# 1_47.net
KiCad netlist of a schematic drawn in Altium Designer
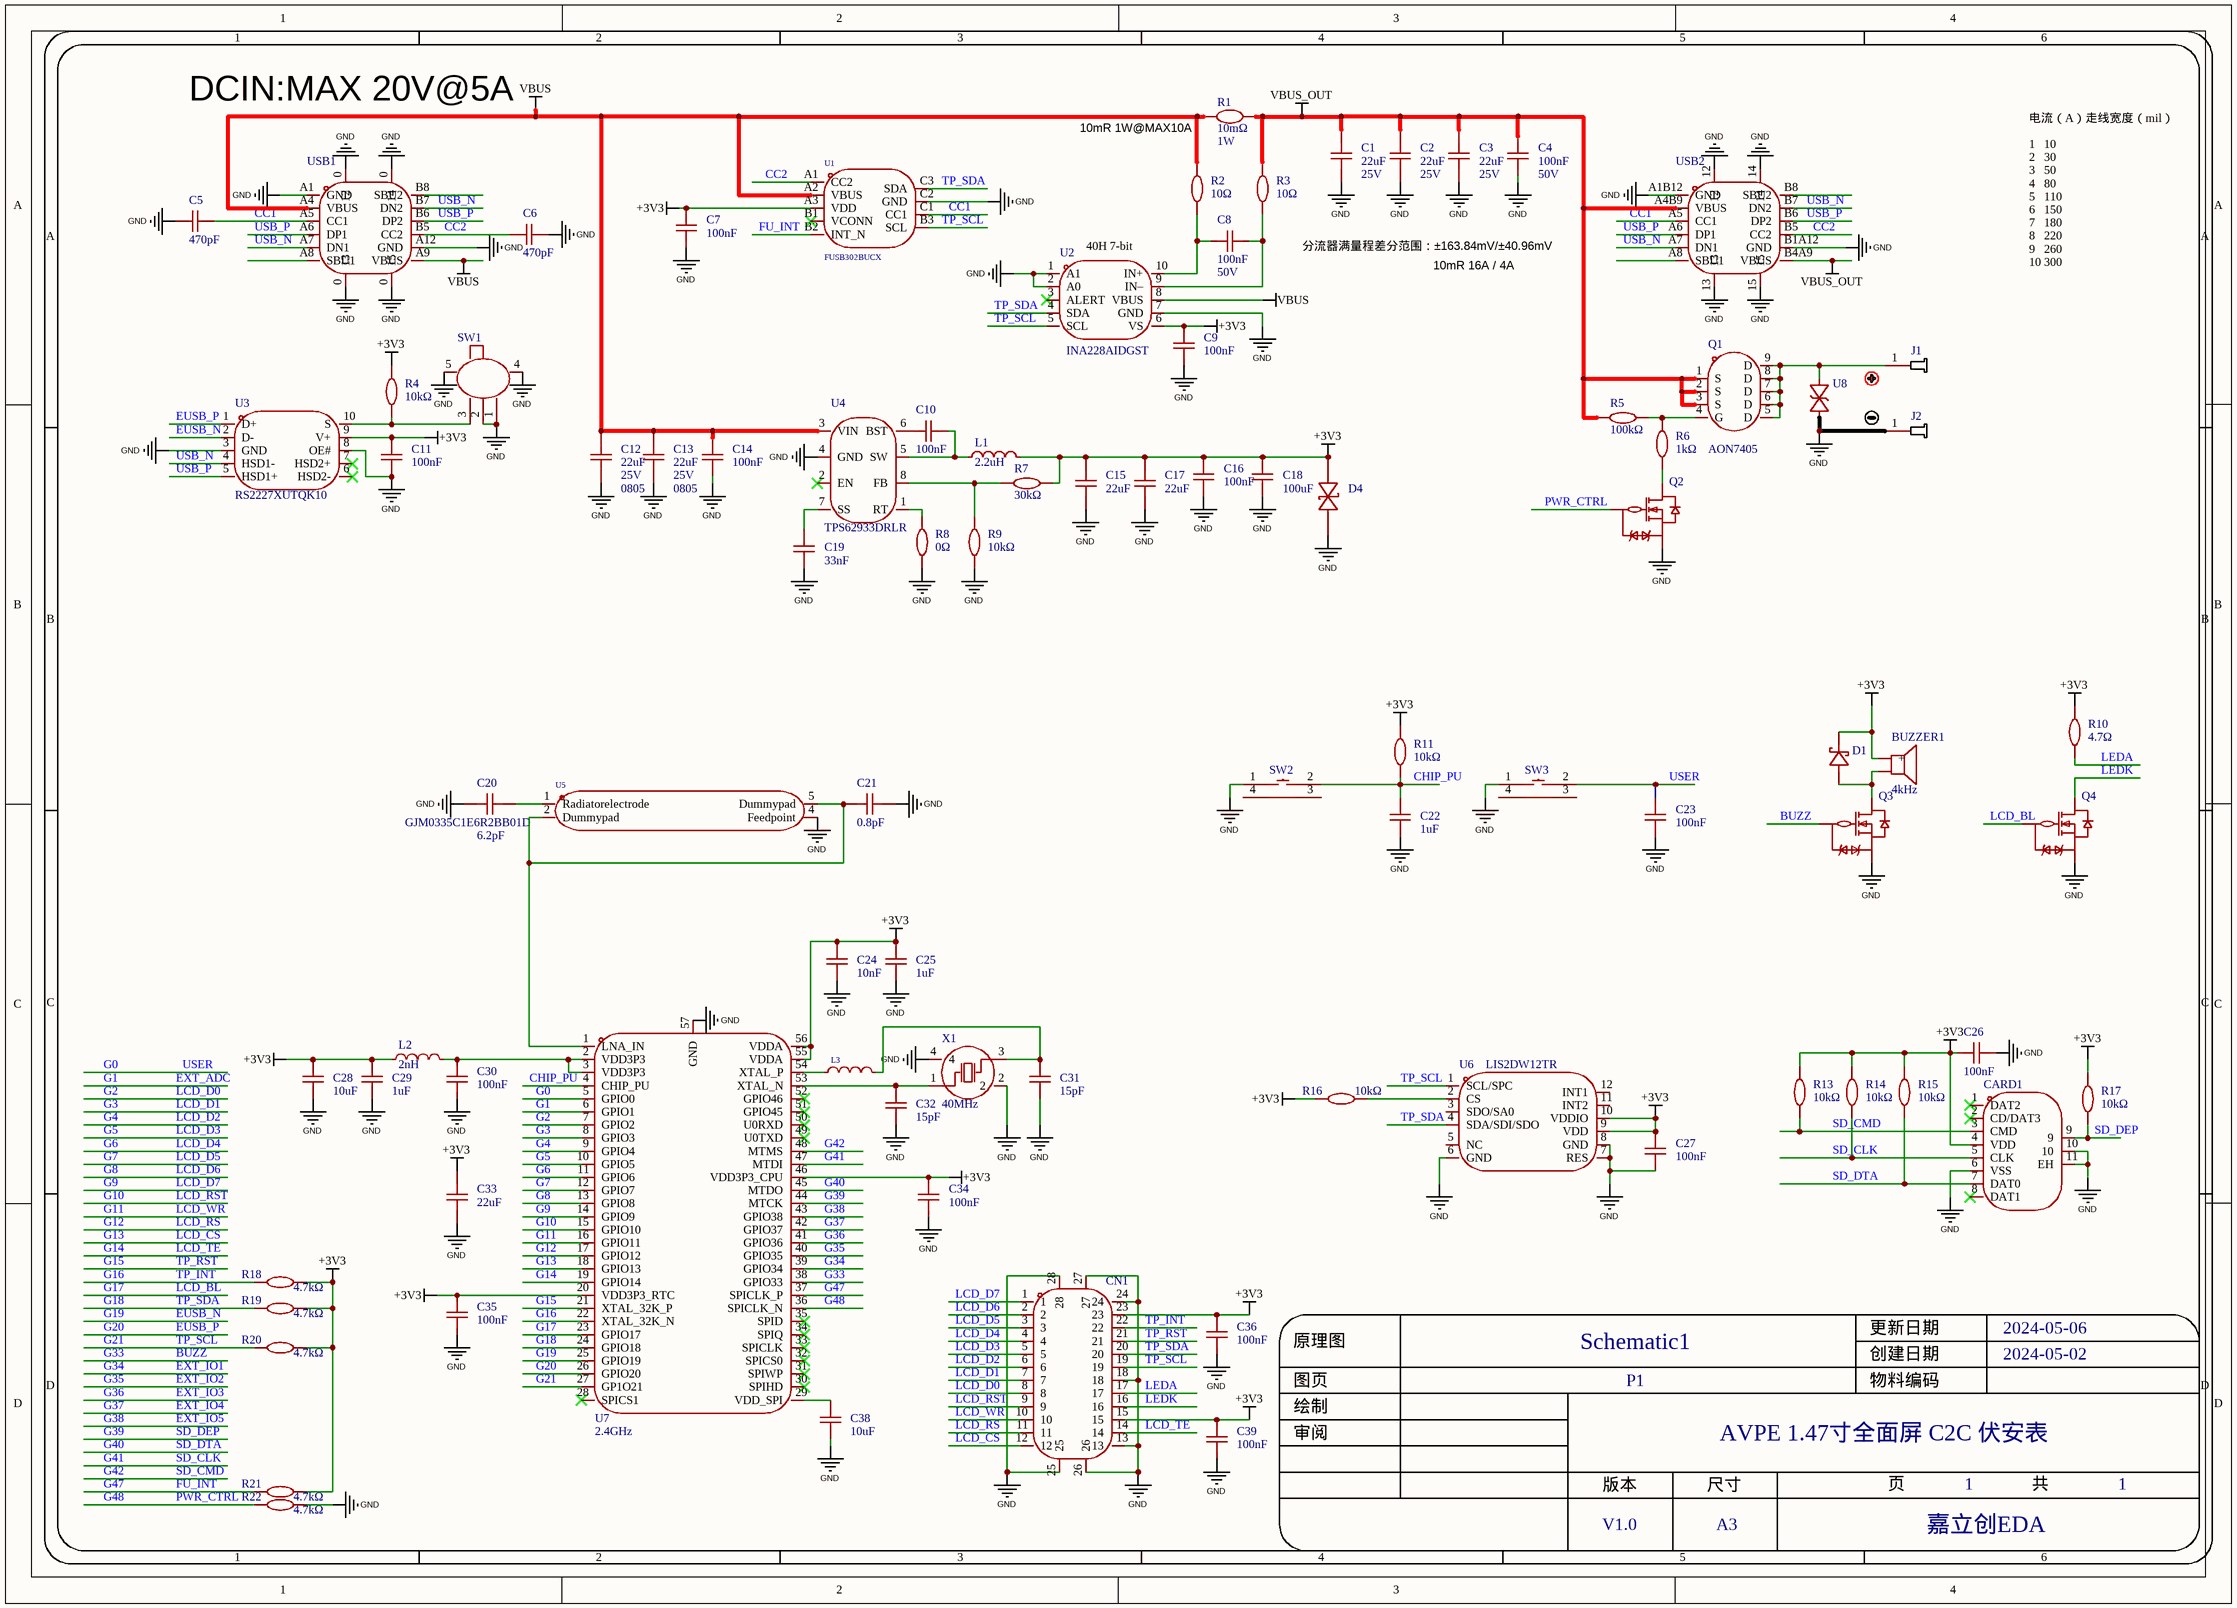
[diagram p0: 1.47.schdoc]

(export (version "E")
  (design (tool "Eeschema 10.0.6"))
  (components
    (comp (ref "BUZZER1")
      (value "4kHz")
      (footprint "BUZ-SMD_L4.0-W4.0-P3.50-L")
      (description "驱动方式:无源(外部驱动);构造类型:电磁式;频率:4kHz;声压(SPL):65dB@3V,10cm;")
      (fields (field (name "MANUFACTURER") "FUET(福声科技)") (field (name "MANUFACTURER PART") "FUET-4020"))
      (libsource (lib "altium-import") (part "root_0_FUET-4020_"))
    )
    (comp (ref "C1")
      (value "22uF")
      (footprint "C1206")
      (description "容值:22uF;精度:±10%;额定电压:25V;材质(温度系数):X5R;")
      (fields
        (field (name "MANUFACTURER") "Chinocera(华瓷)")
        (field (name "MANUFACTURER PART") "HGC1206R5226K250NSPJ")
        (field (name "VOLTAGE RATED") "25V")
      )
      (libsource (lib "altium-import") (part "root_1_HGC1206R5226K250NSPJ_"))
    )
    (comp (ref "C2")
      (value "22uF")
      (footprint "C1206")
      (description "容值:22uF;精度:±10%;额定电压:25V;材质(温度系数):X5R;")
      (fields
        (field (name "MANUFACTURER") "Chinocera(华瓷)")
        (field (name "MANUFACTURER PART") "HGC1206R5226K250NSPJ")
        (field (name "VOLTAGE RATED") "25V")
      )
      (libsource (lib "altium-import") (part "root_1_HGC1206R5226K250NSPJ_"))
    )
    (comp (ref "C3")
      (value "22uF")
      (footprint "C1206")
      (description "容值:22uF;精度:±10%;额定电压:25V;材质(温度系数):X5R;")
      (fields
        (field (name "MANUFACTURER") "Chinocera(华瓷)")
        (field (name "MANUFACTURER PART") "HGC1206R5226K250NSPJ")
        (field (name "VOLTAGE RATED") "25V")
      )
      (libsource (lib "altium-import") (part "root_1_HGC1206R5226K250NSPJ_"))
    )
    (comp (ref "C4")
      (value "100nF")
      (footprint "C0402")
      (description "容值:100nF;精度:±10%;额定电压:50V;材质(温度系数):X7R;")
      (fields
        (field (name "MANUFACTURER") "SAMSUNG(三星)")
        (field (name "MANUFACTURER PART") "CL05B104KB54PNC")
        (field (name "VOLTAGE RATED") "50V")
      )
      (libsource (lib "altium-import") (part "root_1_CL05B104KB54PNC_"))
    )
    (comp (ref "C5")
      (value "470pF")
      (footprint "C0402")
      (description "容值:470pF;精度:±10%;额定电压:50V;材质(温度系数):X7R;")
      (fields (field (name "MANUFACTURER") "FH(风华)") (field (name "MANUFACTURER PART") "0402B471K500NT"))
      (libsource (lib "altium-import") (part "root_2_0402B471K500NT_"))
    )
    (comp (ref "C6")
      (value "470pF")
      (footprint "C0402")
      (description "容值:470pF;精度:±10%;额定电压:50V;材质(温度系数):X7R;")
      (fields (field (name "MANUFACTURER") "FH(风华)") (field (name "MANUFACTURER PART") "0402B471K500NT"))
      (libsource (lib "altium-import") (part "root_2_0402B471K500NT_"))
    )
    (comp (ref "C7")
      (value "100nF")
      (footprint "C0402")
      (description "容值:100nF;精度:±10%;额定电压:50V;材质(温度系数):X7R;")
      (fields
        (field (name "MANUFACTURER") "SAMSUNG(三星)")
        (field (name "MANUFACTURER PART") "CL05B104KB54PNC")
      )
      (libsource (lib "altium-import") (part "root_3_CL05B104KB54PNC_"))
    )
    (comp (ref "C8")
      (value "100nF")
      (footprint "C0402")
      (description "容值:100nF;精度:±10%;额定电压:50V;材质(温度系数):X7R;")
      (fields
        (field (name "MANUFACTURER") "SAMSUNG(三星)")
        (field (name "MANUFACTURER PART") "CL05B104KB54PNC")
        (field (name "VOLTAGE RATED") "50V")
      )
      (libsource (lib "altium-import") (part "root_2_CL05B104KB54PNC_"))
    )
    (comp (ref "C9")
      (value "100nF")
      (footprint "C0402")
      (description "容值:100nF;精度:±10%;额定电压:50V;材质(温度系数):X7R;")
      (fields
        (field (name "MANUFACTURER") "SAMSUNG(三星)")
        (field (name "MANUFACTURER PART") "CL05B104KB54PNC")
      )
      (libsource (lib "altium-import") (part "root_3_CL05B104KB54PNC_"))
    )
    (comp (ref "C10")
      (value "100nF")
      (footprint "C0402")
      (description "容值:100nF;精度:±10%;额定电压:50V;材质(温度系数):X7R;")
      (fields
        (field (name "MANUFACTURER") "SAMSUNG(三星)")
        (field (name "MANUFACTURER PART") "CL05B104KB54PNC")
      )
      (libsource (lib "altium-import") (part "root_2_CL05B104KB54PNC_"))
    )
    (comp (ref "C11")
      (value "100nF")
      (footprint "C0402")
      (description "容值:100nF;精度:±10%;额定电压:50V;材质(温度系数):X7R;")
      (fields
        (field (name "MANUFACTURER") "SAMSUNG(三星)")
        (field (name "MANUFACTURER PART") "CL05B104KB54PNC")
      )
      (libsource (lib "altium-import") (part "root_3_CL05B104KB54PNC_"))
    )
    (comp (ref "C12")
      (value "22uF")
      (footprint "C0805")
      (description "容值:22uF;精度:±20%;额定电压:25V;材质(温度系数):X5R;")
      (fields
        (field (name "MANUFACTURER") "SAMSUNG(三星)")
        (field (name "MANUFACTURER PART") "CL21A226MAYNNNE")
        (field (name "SUPPLIER FOOTPRINT") "0805")
        (field (name "VOLTAGE RATED") "25V")
      )
      (libsource (lib "altium-import") (part "root_1_CL21A226MAYNNNE_"))
    )
    (comp (ref "C13")
      (value "22uF")
      (footprint "C0805")
      (description "容值:22uF;精度:±20%;额定电压:25V;材质(温度系数):X5R;")
      (fields
        (field (name "MANUFACTURER") "SAMSUNG(三星)")
        (field (name "MANUFACTURER PART") "CL21A226MAYNNNE")
        (field (name "SUPPLIER FOOTPRINT") "0805")
        (field (name "VOLTAGE RATED") "25V")
      )
      (libsource (lib "altium-import") (part "root_1_CL21A226MAYNNNE_"))
    )
    (comp (ref "C14")
      (value "100nF")
      (footprint "C0402")
      (description "容值:100nF;精度:±10%;额定电压:50V;材质(温度系数):X7R;")
      (fields
        (field (name "MANUFACTURER") "SAMSUNG(三星)")
        (field (name "MANUFACTURER PART") "CL05B104KB54PNC")
      )
      (libsource (lib "altium-import") (part "root_3_CL05B104KB54PNC_"))
    )
    (comp (ref "C15")
      (value "22uF")
      (footprint "C0603")
      (description "容值:22uF;精度:±20%;额定电压:10V;材质(温度系数):X5R;")
      (fields
        (field (name "MANUFACTURER") "SAMSUNG(三星)")
        (field (name "MANUFACTURER PART") "CL10A226MP8NUNE")
      )
      (libsource (lib "altium-import") (part "root_1_CL10A226MP8NUNE_"))
    )
    (comp (ref "C16")
      (value "100nF")
      (footprint "C0402")
      (description "容值:100nF;精度:±10%;额定电压:50V;材质(温度系数):X7R;")
      (fields
        (field (name "MANUFACTURER") "SAMSUNG(三星)")
        (field (name "MANUFACTURER PART") "CL05B104KB54PNC")
      )
      (libsource (lib "altium-import") (part "root_3_CL05B104KB54PNC_"))
    )
    (comp (ref "C17")
      (value "22uF")
      (footprint "C0603")
      (description "容值:22uF;精度:±20%;额定电压:10V;材质(温度系数):X5R;")
      (fields
        (field (name "MANUFACTURER") "SAMSUNG(三星)")
        (field (name "MANUFACTURER PART") "CL10A226MP8NUNE")
      )
      (libsource (lib "altium-import") (part "root_1_CL10A226MP8NUNE_"))
    )
    (comp (ref "C18")
      (value "100uF")
      (footprint "C1206")
      (description "容值:100uF;精度:±20%;额定电压:6.3V;材质(温度系数):X5R;")
      (fields
        (field (name "MANUFACTURER PART") "CL31A107MQHNNNE")
        (field (name "MANUFACTURER") "SAMSUNG(三星)")
      )
      (libsource (lib "altium-import") (part "root_1_CL31A107MQHNNNE_"))
    )
    (comp (ref "C19")
      (value "33nF")
      (footprint "C0402")
      (description "容值:33nF;精度:±10%;额定电压:50V;材质(温度系数):X7R;")
      (fields
        (field (name "MANUFACTURER") "YAGEO(国巨)")
        (field (name "MANUFACTURER PART") "CC0402KRX7R9BB333")
      )
      (libsource (lib "altium-import") (part "root_1_CC0402KRX7R9BB333_"))
    )
    (comp (ref "C20")
      (value "6.2pF")
      (footprint "C0201")
      (description "容值:0.8pF;额定电压:25V;材质(温度系数):C0G;")
      (fields
        (field (name "MANUFACTURER") "muRata(村田)")
        (field (name "MANUFACTURER PART") "GJM0335C1E6R2BB01D")
      )
      (libsource (lib "altium-import") (part "root_2_mirrored_GJM0335C1ER80WB01D_"))
    )
    (comp (ref "C21")
      (value "0.8pF")
      (footprint "C0402")
      (description "容值:0.8pF;额定电压:25V;材质(温度系数):C0G;")
      (fields
        (field (name "MANUFACTURER") "muRata(村田)")
        (field (name "MANUFACTURER PART") "GJM0335C1ER80WB01D")
      )
      (libsource (lib "altium-import") (part "root_2_mirrored_GJM0335C1ER80WB01D_"))
    )
    (comp (ref "C22")
      (value "1uF")
      (footprint "C0402")
      (description "容值:1uF;精度:±10%;额定电压:10V;材质(温度系数):X5R;")
      (fields
        (field (name "MANUFACTURER PART") "CL05A105KP5NNNC")
        (field (name "MANUFACTURER") "SAMSUNG(三星)")
      )
      (libsource (lib "altium-import") (part "root_1_CL05A105KP5NNNC_"))
    )
    (comp (ref "C23")
      (value "100nF")
      (footprint "C0402")
      (description "容值:100nF;精度:±10%;额定电压:50V;材质(温度系数):X7R;")
      (fields
        (field (name "MANUFACTURER") "SAMSUNG(三星)")
        (field (name "MANUFACTURER PART") "CL05B104KB54PNC")
      )
      (libsource (lib "altium-import") (part "root_3_CL05B104KB54PNC_"))
    )
    (comp (ref "C24")
      (value "10nF")
      (footprint "C0402")
      (description "容值:10nF;精度:±10%;额定电压:50V;材质(温度系数):X7R;")
      (fields
        (field (name "MANUFACTURER") "SAMSUNG(三星)")
        (field (name "MANUFACTURER PART") "CL05B103KB5NNNC")
      )
      (libsource (lib "altium-import") (part "root_1_CL05B103KB5NNNC_"))
    )
    (comp (ref "C25")
      (value "1uF")
      (footprint "C0402")
      (description "容值:1uF;精度:±10%;额定电压:10V;材质(温度系数):X5R;")
      (fields
        (field (name "MANUFACTURER PART") "CL05A105KP5NNNC")
        (field (name "MANUFACTURER") "SAMSUNG(三星)")
      )
      (libsource (lib "altium-import") (part "root_1_CL05A105KP5NNNC_"))
    )
    (comp (ref "C26")
      (value "100nF")
      (footprint "C0402")
      (description "容值:100nF;精度:±10%;额定电压:50V;材质(温度系数):X7R;")
      (fields
        (field (name "MANUFACTURER") "SAMSUNG(三星)")
        (field (name "MANUFACTURER PART") "CL05B104KB54PNC")
      )
      (libsource (lib "altium-import") (part "root_0_CL05B104KB54PNC_"))
    )
    (comp (ref "C27")
      (value "100nF")
      (footprint "C0402")
      (description "容值:100nF;精度:±10%;额定电压:50V;材质(温度系数):X7R;")
      (fields
        (field (name "MANUFACTURER") "SAMSUNG(三星)")
        (field (name "MANUFACTURER PART") "CL05B104KB54PNC")
      )
      (libsource (lib "altium-import") (part "root_1_CL05B104KB54PNC_"))
    )
    (comp (ref "C28")
      (value "10uF")
      (footprint "C0402")
      (description "容值:10uF;精度:±20%;额定电压:6.3V;材质(温度系数):X5R;")
      (fields
        (field (name "MANUFACTURER PART") "CL05A106MQ5NUNC")
        (field (name "MANUFACTURER") "SAMSUNG(三星)")
      )
      (libsource (lib "altium-import") (part "root_1_CL05A106MQ5NUNC_"))
    )
    (comp (ref "C29")
      (value "1uF")
      (footprint "C0402")
      (description "容值:1uF;精度:±10%;额定电压:10V;材质(温度系数):X5R;")
      (fields
        (field (name "MANUFACTURER PART") "CL05A105KP5NNNC")
        (field (name "MANUFACTURER") "SAMSUNG(三星)")
      )
      (libsource (lib "altium-import") (part "root_1_CL05A105KP5NNNC_"))
    )
    (comp (ref "C30")
      (value "100nF")
      (footprint "C0402")
      (description "容值:100nF;精度:±10%;额定电压:50V;材质(温度系数):X7R;")
      (fields
        (field (name "MANUFACTURER") "SAMSUNG(三星)")
        (field (name "MANUFACTURER PART") "CL05B104KB54PNC")
      )
      (libsource (lib "altium-import") (part "root_3_CL05B104KB54PNC_"))
    )
    (comp (ref "C31")
      (value "15pF")
      (footprint "C0402")
      (description "容值:15pF;精度:±5%;额定电压:50V;材质(温度系数):C0G;")
      (fields (field (name "MANUFACTURER") "FH(风华)") (field (name "MANUFACTURER PART") "0402CG150J500NT"))
      (libsource (lib "altium-import") (part "root_1_0402CG150J500NT_"))
    )
    (comp (ref "C32")
      (value "15pF")
      (footprint "C0402")
      (description "容值:15pF;精度:±5%;额定电压:50V;材质(温度系数):C0G;")
      (fields (field (name "MANUFACTURER") "FH(风华)") (field (name "MANUFACTURER PART") "0402CG150J500NT"))
      (libsource (lib "altium-import") (part "root_1_0402CG150J500NT_"))
    )
    (comp (ref "C33")
      (value "22uF")
      (footprint "C0603")
      (description "容值:22uF;精度:±20%;额定电压:10V;材质(温度系数):X5R;")
      (fields
        (field (name "MANUFACTURER") "SAMSUNG(三星)")
        (field (name "MANUFACTURER PART") "CL10A226MP8NUNE")
      )
      (libsource (lib "altium-import") (part "root_1_CL10A226MP8NUNE_"))
    )
    (comp (ref "C34")
      (value "100nF")
      (footprint "C0402")
      (description "容值:100nF;精度:±10%;额定电压:50V;材质(温度系数):X7R;")
      (fields
        (field (name "MANUFACTURER") "SAMSUNG(三星)")
        (field (name "MANUFACTURER PART") "CL05B104KB54PNC")
      )
      (libsource (lib "altium-import") (part "root_3_mirrored_CL05B104KB54PNC_"))
    )
    (comp (ref "C35")
      (value "100nF")
      (footprint "C0402")
      (description "容值:100nF;精度:±10%;额定电压:50V;材质(温度系数):X7R;")
      (fields
        (field (name "MANUFACTURER") "SAMSUNG(三星)")
        (field (name "MANUFACTURER PART") "CL05B104KB54PNC")
      )
      (libsource (lib "altium-import") (part "root_3_CL05B104KB54PNC_"))
    )
    (comp (ref "C36")
      (value "100nF")
      (footprint "C0402")
      (description "容值:100nF;精度:±10%;额定电压:50V;材质(温度系数):X7R;")
      (fields
        (field (name "MANUFACTURER") "SAMSUNG(三星)")
        (field (name "MANUFACTURER PART") "CL05B104KB54PNC")
      )
      (libsource (lib "altium-import") (part "root_3_mirrored_CL05B104KB54PNC_"))
    )
    (comp (ref "C38")
      (value "10uF")
      (footprint "C0402")
      (description "容值:10uF;精度:±20%;额定电压:6.3V;材质(温度系数):X5R;")
      (fields
        (field (name "MANUFACTURER PART") "CL05A106MQ5NUNC")
        (field (name "MANUFACTURER") "SAMSUNG(三星)")
      )
      (libsource (lib "altium-import") (part "root_1_CL05A106MQ5NUNC_"))
    )
    (comp (ref "C39")
      (value "100nF")
      (footprint "C0402")
      (description "容值:100nF;精度:±10%;额定电压:50V;材质(温度系数):X7R;")
      (fields
        (field (name "MANUFACTURER") "SAMSUNG(三星)")
        (field (name "MANUFACTURER PART") "CL05B104KB54PNC")
      )
      (libsource (lib "altium-import") (part "root_3_mirrored_CL05B104KB54PNC_"))
    )
    (comp (ref "CARD1")
      (value "5033981892")
      (footprint "TF-SMD_TF-110")
      (description "卡连接方式:自弹式;卡类型:MicroSD卡(TF卡);连接器类型:卡座;本体最大高度:1.28mm;触头镀层:金;工作温度范围:-25℃~+85℃;")
      (fields (field (name "MANUFACTURER") "MOLEX"))
      (libsource (lib "altium-import") (part "root_0_5033981892_"))
    )
    (comp (ref "CN1")
      (value "BM20B(0.8)-24DS-0.4V(51)")
      (footprint "CONN-SMD_BM20B-0.8-24DS-0.4V-51")
      (description "PIN总数:-;间距:0.4mm;公母:母;安装方式:立贴;行数:2;额定电流:300mA;工作温度范围:-35℃~+85℃;")
      (fields (field (name "MANUFACTURER") "HRS(广濑)"))
      (libsource (lib "1.47") (part "BM20B(0.8)-24DS-0.4V(51)"))
    )
    (comp (ref "D1")
      (value "1N4148WT")
      (footprint "SOD-523_L1.2-W0.8-LS1.6-RD")
      (description "二极管配置:独立式;正向压降(Vf):1.25V@150mA;直流反向耐压(Vr):75V;平均整流电流(Io):125mA;反向恢复时间(trr):4ns;")
      (fields (field (name "MANUFACTURER") "TWGMC(台湾迪嘉)"))
      (libsource (lib "altium-import") (part "root_3_1N4148WT_C727112_"))
    )
    (comp (ref "D4")
      (value "BDFN2C031V")
      (footprint "TSSLP-2-4_L1.0-W0.6-P0.65-BI")
      (description "反向截止电压(Vrwm):3.3V;最大钳位电压:8V;峰值脉冲电流(Ipp)@10/1000us:11A@8/20us;击穿电压:3.7V;")
      (fields (field (name "MANUFACTURER") "BORN(伯恩半导体)"))
      (libsource (lib "altium-import") (part "root_1_BDFN2C031V_"))
    )
    (comp (ref "J1")
      (value "~")
      (footprint "Banana_M2xφ4.4x7_2")
      (description "K2台阶插座,Banana_M2xφ4.4x7")
      (libsource (lib "altium-import") (part "root_0_Banana_M2xφ4.4x7_"))
    )
    (comp (ref "J2")
      (value "~")
      (footprint "Banana_M2xφ4.4x7_2")
      (description "K2台阶插座,Banana_M2xφ4.4x7")
      (libsource (lib "altium-import") (part "root_0_Banana_M2xφ4.4x7_"))
    )
    (comp (ref "L1")
      (value "2.2uH")
      (footprint "L0805")
      (description "电感值:2.2uH;精度:±20%;额定电流:1A;")
      (fields (field (name "MANUFACTURER") "TDK") (field (name "MANUFACTURER PART") "MLP2012H2R2MT0S1"))
      (libsource (lib "altium-import") (part "root_0_MLP2012H2R2MT0S1_"))
    )
    (comp (ref "L2")
      (value "2nH")
      (footprint "L0402")
      (description "电感值:2nH;精度:-;额定电流:300mA;饱和电流(Isat):-;直流电阻(DCR):200mΩ;")
      (fields
        (field (name "MANUFACTURER") "Sunlord(顺络)")
        (field (name "MANUFACTURER PART") "SDCL1005C2N0STDF")
      )
      (libsource (lib "altium-import") (part "root_0_SDCL1005C2N0STDF_"))
    )
    (comp (ref "L3")
      (value "27nH")
      (footprint "IND-SMD_L1.0-W0.5-2")
      (description "电感值:27nH;精度:±2%;额定电流:280mA;饱和电流(Isat):-;")
      (fields (field (name "MANUFACTURER") "muRata(村田)") (field (name "MANUFACTURER PART") "LQW15AN27NG00D"))
      (libsource (lib "altium-import") (part "root_0_LQW15AN27NG00D_"))
    )
    (comp (ref "Q1")
      (value "AON7405")
      (footprint "DFN-8_L3.3-W3.3-P0.65-BL-3")
      (fields (field (name "MANUFACTURER") "AOS") (field (name "MANUFACTURER PART") "AON7405"))
      (libsource (lib "altium-import") (part "root_0_AON7405_"))
    )
    (comp (ref "Q2")
      (value "WNM6002-3/TR")
      (footprint "SOT-323-3_L2.0-W1.3-P1.30-LS2.1-BR")
      (fields (field (name "MANUFACTURER") "WILLSEMI(韦尔)"))
      (libsource (lib "altium-import") (part "root_0_WNM6002-3/TR_"))
    )
    (comp (ref "Q3")
      (value "WNM6002-3/TR")
      (footprint "SOT-323-3_L2.0-W1.3-P1.30-LS2.1-BR")
      (fields (field (name "MANUFACTURER") "WILLSEMI(韦尔)"))
      (libsource (lib "altium-import") (part "root_0_WNM6002-3/TR_"))
    )
    (comp (ref "Q4")
      (value "WNM6002-3/TR")
      (footprint "SOT-323-3_L2.0-W1.3-P1.30-LS2.1-BR")
      (fields (field (name "MANUFACTURER") "WILLSEMI(韦尔)"))
      (libsource (lib "altium-import") (part "root_0_WNM6002-3/TR_"))
    )
    (comp (ref "R1")
      (value "10mΩ")
      (footprint "RES-SMD_L6.3-W3.3_HOLR2512")
      (description "电阻类型:采样电阻;阻值:10mΩ;精度:±1%;功率:1W;温度系数:±15ppm/℃;安装方式:贴片;")
      (fields
        (field (name "MANUFACTURER") "Milliohm(毫欧)")
        (field (name "MANUFACTURER PART") "HoLR2512-1W-10mR-1%-15ppm")
        (field (name "POWER(WATTS)") "1W")
      )
      (libsource (lib "altium-import") (part "root_0_HoLR2512-1W-10mR-1%-15ppm_"))
    )
    (comp (ref "R2")
      (value "10Ω")
      (footprint "R0402")
      (description "电阻类型:厚膜电阻;阻值:10Ω;精度:±1%;功率:62.5mW;最大工作电压:50V;温度系数:±200ppm/℃;")
      (fields
        (field (name "MANUFACTURER") "UNI-ROYAL(厚声)")
        (field (name "MANUFACTURER PART") "0402WGF100JTCE")
      )
      (libsource (lib "altium-import") (part "root_1_0402WGF100JTCE_"))
    )
    (comp (ref "R3")
      (value "10Ω")
      (footprint "R0402")
      (description "电阻类型:厚膜电阻;阻值:10Ω;精度:±1%;功率:62.5mW;最大工作电压:50V;温度系数:±200ppm/℃;")
      (fields
        (field (name "MANUFACTURER") "UNI-ROYAL(厚声)")
        (field (name "MANUFACTURER PART") "0402WGF100JTCE")
      )
      (libsource (lib "altium-import") (part "root_1_0402WGF100JTCE_"))
    )
    (comp (ref "R4")
      (value "10kΩ")
      (footprint "R0402")
      (description "电阻类型:厚膜电阻;阻值:10kΩ;精度:±1%;功率:62.5mW;最大工作电压:50V;温度系数:±100ppm/℃;")
      (fields
        (field (name "MANUFACTURER") "UNI-ROYAL(厚声)")
        (field (name "MANUFACTURER PART") "0402WGF1002TCE")
      )
      (libsource (lib "altium-import") (part "root_1_0402WGF1002TCE_"))
    )
    (comp (ref "R5")
      (value "100kΩ")
      (footprint "R0402")
      (description "电阻类型:厚膜电阻;阻值:100kΩ;精度:±1%;功率:62.5mW;最大工作电压:50V;温度系数:±100ppm/℃;")
      (fields
        (field (name "MANUFACTURER") "UNI-ROYAL(厚声)")
        (field (name "MANUFACTURER PART") "0402WGF1003TCE")
      )
      (libsource (lib "altium-import") (part "root_2_0402WGF1003TCE_"))
    )
    (comp (ref "R6")
      (value "1kΩ")
      (footprint "R0402")
      (description "电阻类型:厚膜电阻;阻值:1kΩ;精度:±1%;功率:62.5mW;最大工作电压:50V;温度系数:±100ppm/℃;")
      (fields
        (field (name "MANUFACTURER") "UNI-ROYAL(厚声)")
        (field (name "MANUFACTURER PART") "0402WGF1001TCE")
      )
      (libsource (lib "altium-import") (part "root_1_0402WGF1001TCE_"))
    )
    (comp (ref "R7")
      (value "30kΩ")
      (footprint "R0402")
      (description "电阻类型:厚膜电阻;阻值:30kΩ;精度:±1%;功率:62.5mW;最大工作电压:50V;温度系数:±100ppm/℃;")
      (fields
        (field (name "MANUFACTURER") "UNI-ROYAL(厚声)")
        (field (name "MANUFACTURER PART") "0402WGF3002TCE")
      )
      (libsource (lib "altium-import") (part "root_0_0402WGF3002TCE_"))
    )
    (comp (ref "R8")
      (value "0Ω")
      (footprint "R0402")
      (description "电阻类型:厚膜电阻;阻值:0Ω;精度:±1%;功率:62.5mW;最大工作电压:50V;温度系数:±800ppm/℃;")
      (fields
        (field (name "MANUFACTURER") "UNI-ROYAL(厚声)")
        (field (name "MANUFACTURER PART") "0402WGF0000TCE")
      )
      (libsource (lib "altium-import") (part "root_1_0402WGF0000TCE_"))
    )
    (comp (ref "R9")
      (value "10kΩ")
      (footprint "R0402")
      (description "电阻类型:厚膜电阻;阻值:10kΩ;精度:±1%;功率:62.5mW;最大工作电压:50V;温度系数:±100ppm/℃;")
      (fields
        (field (name "MANUFACTURER") "UNI-ROYAL(厚声)")
        (field (name "MANUFACTURER PART") "0402WGF1002TCE")
      )
      (libsource (lib "altium-import") (part "root_1_0402WGF1002TCE_"))
    )
    (comp (ref "R10")
      (value "4.7Ω")
      (footprint "R0603")
      (description "电阻类型:厚膜电阻;阻值:4.7Ω;精度:±1%;功率:100mW;最大工作电压:75V;温度系数:±400ppm/℃;")
      (fields
        (field (name "MANUFACTURER") "UNI-ROYAL(厚声)")
        (field (name "MANUFACTURER PART") "0603WAF470KT5E")
      )
      (libsource (lib "altium-import") (part "root_1_0603WAF470KT5E_"))
    )
    (comp (ref "R11")
      (value "10kΩ")
      (footprint "R0402")
      (description "电阻类型:厚膜电阻;阻值:10kΩ;精度:±1%;功率:62.5mW;最大工作电压:50V;温度系数:±100ppm/℃;")
      (fields
        (field (name "MANUFACTURER") "UNI-ROYAL(厚声)")
        (field (name "MANUFACTURER PART") "0402WGF1002TCE")
      )
      (libsource (lib "altium-import") (part "root_1_0402WGF1002TCE_"))
    )
    (comp (ref "R13")
      (value "10kΩ")
      (footprint "R0402")
      (description "电阻类型:厚膜电阻;阻值:10kΩ;精度:±1%;功率:62.5mW;最大工作电压:50V;温度系数:±100ppm/℃;")
      (fields
        (field (name "MANUFACTURER") "UNI-ROYAL(厚声)")
        (field (name "MANUFACTURER PART") "0402WGF1002TCE")
      )
      (libsource (lib "altium-import") (part "root_3_0402WGF1002TCE_"))
    )
    (comp (ref "R14")
      (value "10kΩ")
      (footprint "R0402")
      (description "电阻类型:厚膜电阻;阻值:10kΩ;精度:±1%;功率:62.5mW;最大工作电压:50V;温度系数:±100ppm/℃;")
      (fields
        (field (name "MANUFACTURER") "UNI-ROYAL(厚声)")
        (field (name "MANUFACTURER PART") "0402WGF1002TCE")
      )
      (libsource (lib "altium-import") (part "root_3_0402WGF1002TCE_"))
    )
    (comp (ref "R15")
      (value "10kΩ")
      (footprint "R0402")
      (description "电阻类型:厚膜电阻;阻值:10kΩ;精度:±1%;功率:62.5mW;最大工作电压:50V;温度系数:±100ppm/℃;")
      (fields
        (field (name "MANUFACTURER") "UNI-ROYAL(厚声)")
        (field (name "MANUFACTURER PART") "0402WGF1002TCE")
      )
      (libsource (lib "altium-import") (part "root_3_0402WGF1002TCE_"))
    )
    (comp (ref "R16")
      (value "10kΩ")
      (footprint "R0402")
      (description "电阻类型:厚膜电阻;阻值:10kΩ;精度:±1%;功率:62.5mW;最大工作电压:50V;温度系数:±100ppm/℃;")
      (fields
        (field (name "MANUFACTURER") "UNI-ROYAL(厚声)")
        (field (name "MANUFACTURER PART") "0402WGF1002TCE")
      )
      (libsource (lib "altium-import") (part "root_2_0402WGF1002TCE_"))
    )
    (comp (ref "R17")
      (value "10kΩ")
      (footprint "R0402")
      (description "电阻类型:厚膜电阻;阻值:10kΩ;精度:±1%;功率:62.5mW;最大工作电压:50V;温度系数:±100ppm/℃;")
      (fields
        (field (name "MANUFACTURER") "UNI-ROYAL(厚声)")
        (field (name "MANUFACTURER PART") "0402WGF1002TCE")
      )
      (libsource (lib "altium-import") (part "root_1_0402WGF1002TCE_"))
    )
    (comp (ref "R18")
      (value "4.7kΩ")
      (footprint "R0402")
      (description "电阻类型:厚膜电阻;阻值:4.7kΩ;精度:±1%;功率:62.5mW;最大工作电压:50V;温度系数:±100ppm/℃;")
      (fields
        (field (name "MANUFACTURER") "UNI-ROYAL(厚声)")
        (field (name "MANUFACTURER PART") "0402WGF4701TCE")
      )
      (libsource (lib "altium-import") (part "root_2_0402WGF4701TCE_"))
    )
    (comp (ref "R19")
      (value "4.7kΩ")
      (footprint "R0402")
      (description "电阻类型:厚膜电阻;阻值:4.7kΩ;精度:±1%;功率:62.5mW;最大工作电压:50V;温度系数:±100ppm/℃;")
      (fields
        (field (name "MANUFACTURER") "UNI-ROYAL(厚声)")
        (field (name "MANUFACTURER PART") "0402WGF4701TCE")
      )
      (libsource (lib "altium-import") (part "root_2_0402WGF4701TCE_"))
    )
    (comp (ref "R20")
      (value "4.7kΩ")
      (footprint "R0402")
      (description "电阻类型:厚膜电阻;阻值:4.7kΩ;精度:±1%;功率:62.5mW;最大工作电压:50V;温度系数:±100ppm/℃;")
      (fields
        (field (name "MANUFACTURER") "UNI-ROYAL(厚声)")
        (field (name "MANUFACTURER PART") "0402WGF4701TCE")
      )
      (libsource (lib "altium-import") (part "root_2_0402WGF4701TCE_"))
    )
    (comp (ref "R21")
      (value "4.7kΩ")
      (footprint "R0402")
      (description "电阻类型:厚膜电阻;阻值:4.7kΩ;精度:±1%;功率:62.5mW;最大工作电压:50V;温度系数:±100ppm/℃;")
      (fields
        (field (name "MANUFACTURER") "UNI-ROYAL(厚声)")
        (field (name "MANUFACTURER PART") "0402WGF4701TCE")
      )
      (libsource (lib "altium-import") (part "root_2_0402WGF4701TCE_"))
    )
    (comp (ref "R22")
      (value "4.7kΩ")
      (footprint "R0402")
      (description "电阻类型:厚膜电阻;阻值:4.7kΩ;精度:±1%;功率:62.5mW;最大工作电压:50V;温度系数:±100ppm/℃;")
      (fields
        (field (name "MANUFACTURER") "UNI-ROYAL(厚声)")
        (field (name "MANUFACTURER PART") "0402WGF4701TCE")
      )
      (libsource (lib "altium-import") (part "root_2_0402WGF4701TCE_"))
    )
    (comp (ref "SW1")
      (value "MINI MSK12CO2")
      (footprint "SW-SMD_MSK12CO2")
      (description "电路结构:单刀双掷;安装方式:卧贴;开关颜色:-;额定电流(DC):50mA;额定电压(DC):12V;额定电流(AC):-;额定电压(AC):-;机械寿命:1万次;")
      (fields (field (name "MANUFACTURER") "SHOU HAN(首韩)"))
      (libsource (lib "altium-import") (part "root_2_MINI MSK12CO2_"))
    )
    (comp (ref "SW2")
      (value "GT-TC021B-H018-L1")
      (footprint "SW-SMD_GT-TC021B-H018-L1")
      (fields (field (name "MANUFACTURER") "G-Switch(品赞)"))
      (libsource (lib "altium-import") (part "root_0_GT-TC021B-H018-L1_"))
    )
    (comp (ref "SW3")
      (value "GT-TC021B-H018-L1")
      (footprint "SW-SMD_GT-TC021B-H018-L1")
      (fields (field (name "MANUFACTURER") "G-Switch(品赞)"))
      (libsource (lib "altium-import") (part "root_0_GT-TC021B-H018-L1_"))
    )
    (comp (ref "U1")
      (value "FUSB302BUCX")
      (footprint "WLCSP-9_L1.3-W1.2-R3-C3-P0.40-TL")
      (description "应用功能:控制器;接口协议:USB;")
      (fields (field (name "MANUFACTURER") "onsemi(安森美)") (field (name "MANUFACTURER PART") "FUSB302BUCX"))
      (libsource (lib "altium-import") (part "root_0_FUSB302BUCX_"))
    )
    (comp (ref "U2")
      (value "INA228AIDGST")
      (footprint "VSSOP-10_L3.0-W3.0-P0.50-LS4.9-BL")
      (fields (field (name "MANUFACTURER") "TI(德州仪器)") (field (name "MANUFACTURER PART") "INA228AIDGST"))
      (libsource (lib "altium-import") (part "root_0_INA228AIDGST_"))
    )
    (comp (ref "U3")
      (value "RS2227XUTQK10")
      (footprint "WQFN-10_L1.8-W1.4-P0.40-BL")
      (description "开关电路:-;")
      (fields (field (name "MANUFACTURER") "RUNIC(润石)") (field (name "MANUFACTURER PART") "RS2227XUTQK10"))
      (libsource (lib "altium-import") (part "root_0_RS2227XUTQK10_"))
    )
    (comp (ref "U4")
      (value "TPS62933DRLR")
      (footprint "SOT-583-8_L2.1-W1.2-P0.50-LS1.6-BR")
      (description "功能类型:降压型;输出类型:可调;输入电压:3.8V~30V;输出电压:800mV~22V;输出电流(最大值):3A;")
      (fields (field (name "MANUFACTURER") "TI(德州仪器)") (field (name "MANUFACTURER PART") "TPS62933DRLR"))
      (libsource (lib "altium-import") (part "root_0_TPS62933DRLR_"))
    )
    (comp (ref "U5")
      (value "ANT162442ST-1000AM1")
      (footprint "ANT-SMD_6P-L1.6-W0.8-L")
      (description "天线类型:芯片天线;中心频点:2.442GHz;驻波比:3;")
      (fields (field (name "MANUFACTURER") "TDK"))
      (libsource (lib "altium-import") (part "root_0_ANT162442ST-1000AM1_"))
    )
    (comp (ref "U6")
      (value "LIS2DW12TR")
      (footprint "LGA-12_L2.0-W2.0-P0.50-BL")
      (fields (field (name "MANUFACTURER") "ST(意法半导体)"))
      (libsource (lib "altium-import") (part "root_0_LIS2DW12TR_"))
    )
    (comp (ref "U7")
      (value "2.4GHz")
      (footprint "QFN-56_L7.0-W7.0-P0.40-TL-EP4.0")
      (description "核心处理器:LX7芯片;频率:2.4GHz;天线形式:-;发射功率:21dBm;接收灵敏度:-;")
      (fields
        (field (name "MANUFACTURER") "ESPRESSIF(乐鑫)")
        (field (name "MANUFACTURER PART") "ESP32-S3FH4R2")
      )
      (libsource (lib "altium-import") (part "root_0_ESP32-S3FH4R2_"))
    )
    (comp (ref "U8")
      (value "BDFN2C241R")
      (footprint "DFN1006-2L-BI")
      (description "反向截止电压(Vrwm):24V;")
      (fields (field (name "MANUFACTURER") "BORN(伯恩半导体)"))
      (libsource (lib "altium-import") (part "root_1_BDFN2C241R_"))
    )
    (comp (ref "USB1")
      (value "TYPEC-304A-ACP16O")
      (footprint "USB-TYPE-C-SMD_TYPE-C-16P-QTWT")
      (fields (field (name "MANUFACTURER") "XUNPU(讯普)"))
      (libsource (lib "altium-import") (part "root_0_TYPEC-304A-ACP16O_"))
    )
    (comp (ref "USB2")
      (value "TYPEC-304A-ACP16O")
      (footprint "USB-SMD_TYPEC-304A-ACP16O")
      (fields (field (name "MANUFACTURER") "XUNPU(讯普)"))
      (libsource (lib "") (part "root_0_TYPEC-304A-ACP16O__1"))
    )
    (comp (ref "X1")
      (value "40MHz")
      (footprint "CRYSTAL-SMD_4P-L2.5-W2.0-BL")
      (description "晶振类型:贴片晶振;频率:40MHz;常温频差:±10ppm;外接负载电容:15pF;频率稳定度(全温):±30ppm;")
      (fields
        (field (name "MANUFACTURER") "YJX(雅晶鑫)")
        (field (name "MANUFACTURER PART") "TXM40M0004252HBCEO00T")
      )
      (libsource (lib "altium-import") (part "root_0_TXM40M0004252HBCEO00T_"))
    )
  )
  (nets
    (net (code "1") (name "+3V3") (class "Default")
      (node (ref "BUZZER1") (pin "1") (pinfunction "+_1") (pintype "passive"))
      (node (ref "C11") (pin "1") (pinfunction "1_1") (pintype "passive"))
      (node (ref "C15") (pin "2") (pinfunction "2_2") (pintype "passive"))
      (node (ref "C16") (pin "1") (pinfunction "1_1") (pintype "passive"))
      (node (ref "C17") (pin "2") (pinfunction "2_2") (pintype "passive"))
      (node (ref "C18") (pin "2") (pinfunction "2_2") (pintype "passive"))
      (node (ref "C24") (pin "2") (pinfunction "2_2") (pintype "passive"))
      (node (ref "C25") (pin "2") (pinfunction "2_2") (pintype "passive"))
      (node (ref "C26") (pin "1") (pinfunction "1_1") (pintype "passive"))
      (node (ref "C27") (pin "2") (pinfunction "2_2") (pintype "passive"))
      (node (ref "C28") (pin "2") (pinfunction "2_2") (pintype "passive"))
      (node (ref "C29") (pin "2") (pinfunction "2_2") (pintype "passive"))
      (node (ref "C33") (pin "2") (pinfunction "2_2") (pintype "passive"))
      (node (ref "C34") (pin "1") (pinfunction "1_1") (pintype "passive"))
      (node (ref "C35") (pin "1") (pinfunction "1_1") (pintype "passive"))
      (node (ref "C36") (pin "1") (pinfunction "1_1") (pintype "passive"))
      (node (ref "C39") (pin "1") (pinfunction "1_1") (pintype "passive"))
      (node (ref "C7") (pin "1") (pinfunction "1_1") (pintype "passive"))
      (node (ref "C9") (pin "1") (pinfunction "1_1") (pintype "passive"))
      (node (ref "CARD1") (pin "4") (pinfunction "VDD_4") (pintype "passive"))
      (node (ref "CN1") (pin "15") (pinfunction "15_15") (pintype "passive"))
      (node (ref "CN1") (pin "23") (pinfunction "23_23") (pintype "passive"))
      (node (ref "D1") (pin "1") (pinfunction "C_1") (pintype "passive"))
      (node (ref "D4") (pin "2") (pinfunction "2_2") (pintype "passive"))
      (node (ref "L1") (pin "2") (pinfunction "2_2") (pintype "passive"))
      (node (ref "L2") (pin "1") (pinfunction "1_1") (pintype "passive"))
      (node (ref "R10") (pin "2") (pinfunction "2_2") (pintype "passive"))
      (node (ref "R11") (pin "2") (pinfunction "2_2") (pintype "passive"))
      (node (ref "R13") (pin "1") (pinfunction "1_1") (pintype "passive"))
      (node (ref "R14") (pin "1") (pinfunction "1_1") (pintype "passive"))
      (node (ref "R15") (pin "1") (pinfunction "1_1") (pintype "passive"))
      (node (ref "R16") (pin "2") (pinfunction "2_2") (pintype "passive"))
      (node (ref "R17") (pin "2") (pinfunction "2_2") (pintype "passive"))
      (node (ref "R18") (pin "1") (pinfunction "1_1") (pintype "passive"))
      (node (ref "R19") (pin "1") (pinfunction "1_1") (pintype "passive"))
      (node (ref "R20") (pin "1") (pinfunction "1_1") (pintype "passive"))
      (node (ref "R21") (pin "1") (pinfunction "1_1") (pintype "passive"))
      (node (ref "R4") (pin "2") (pinfunction "2_2") (pintype "passive"))
      (node (ref "R7") (pin "2") (pinfunction "2_2") (pintype "passive"))
      (node (ref "U1") (pin "A3") (pinfunction "VDD_A3") (pintype "passive"))
      (node (ref "U2") (pin "6") (pinfunction "VS_6") (pintype "passive"))
      (node (ref "U3") (pin "9") (pinfunction "V+_9") (pintype "passive"))
      (node (ref "U6") (pin "10") (pinfunction "VDDIO_10") (pintype "passive"))
      (node (ref "U6") (pin "9") (pinfunction "VDD_9") (pintype "passive"))
      (node (ref "U7") (pin "20") (pinfunction "VDD3P3_RTC_20") (pintype "passive"))
      (node (ref "U7") (pin "46") (pinfunction "VDD3P3_CPU_46") (pintype "passive"))
      (node (ref "U7") (pin "55") (pinfunction "VDDA_55") (pintype "passive"))
      (node (ref "U7") (pin "56") (pinfunction "VDDA_56") (pintype "passive"))
    )
    (net (code "2") (name "/BUZZ") (class "Default")
      (node (ref "Q3") (pin "1") (pinfunction "G_1") (pintype "passive"))
      (node (ref "U7") (pin "38") (pinfunction "GPIO33_38") (pintype "passive"))
    )
    (net (code "3") (name "/CC1") (class "Default")
      (node (ref "C5") (pin "1") (pinfunction "1_1") (pintype "passive"))
      (node (ref "U1") (pin "C1") (pinfunction "CC1_C1") (pintype "passive"))
      (node (ref "USB1") (pin "A5") (pinfunction "CC1_A5") (pintype "passive"))
      (node (ref "USB2") (pin "A5") (pinfunction "CC1_A5") (pintype "passive"))
    )
    (net (code "4") (name "/CC2") (class "Default")
      (node (ref "C6") (pin "2") (pinfunction "2_2") (pintype "passive"))
      (node (ref "U1") (pin "A1") (pinfunction "CC2_A1") (pintype "passive"))
      (node (ref "USB1") (pin "B5") (pinfunction "CC2_B5") (pintype "passive"))
      (node (ref "USB2") (pin "B5") (pinfunction "CC2_B5") (pintype "passive"))
    )
    (net (code "5") (name "/CHIP_PU") (class "Default")
      (node (ref "C22") (pin "2") (pinfunction "2_2") (pintype "passive"))
      (node (ref "R11") (pin "1") (pinfunction "1_1") (pintype "passive"))
      (node (ref "SW2") (pin "2") (pinfunction "2_2") (pintype "passive"))
      (node (ref "U7") (pin "4") (pinfunction "CHIP_PU_4") (pintype "passive"))
    )
    (net (code "6") (name "/EUSB_N") (class "Default")
      (node (ref "U3") (pin "2") (pinfunction "D-_2") (pintype "passive"))
      (node (ref "U7") (pin "25") (pinfunction "GPIO19_25") (pintype "passive"))
    )
    (net (code "7") (name "/EUSB_P") (class "Default")
      (node (ref "U3") (pin "1") (pinfunction "D+_1") (pintype "passive"))
      (node (ref "U7") (pin "26") (pinfunction "GPIO20_26") (pintype "passive"))
    )
    (net (code "8") (name "/EXT_ADC") (class "Default")
      (node (ref "U7") (pin "6") (pinfunction "GPIO1_6") (pintype "passive"))
    )
    (net (code "9") (name "/EXT_IO1") (class "Default")
      (node (ref "U7") (pin "39") (pinfunction "GPIO34_39") (pintype "passive"))
    )
    (net (code "10") (name "/EXT_IO2") (class "Default")
      (node (ref "U7") (pin "40") (pinfunction "GPIO35_40") (pintype "passive"))
    )
    (net (code "11") (name "/EXT_IO3") (class "Default")
      (node (ref "U7") (pin "41") (pinfunction "GPIO36_41") (pintype "passive"))
    )
    (net (code "12") (name "/EXT_IO4") (class "Default")
      (node (ref "U7") (pin "42") (pinfunction "GPIO37_42") (pintype "passive"))
    )
    (net (code "13") (name "/EXT_IO5") (class "Default")
      (node (ref "U7") (pin "43") (pinfunction "GPIO38_43") (pintype "passive"))
    )
    (net (code "14") (name "/FU_INT") (class "Default")
      (node (ref "R21") (pin "2") (pinfunction "2_2") (pintype "passive"))
      (node (ref "U1") (pin "B2") (pinfunction "INT_N_B2") (pintype "passive"))
      (node (ref "U7") (pin "37") (pinfunction "SPICLK_P_37") (pintype "passive"))
    )
    (net (code "15") (name "/G0") (class "Default")
      (node (ref "C23") (pin "1") (pinfunction "1_1") (pintype "passive"))
      (node (ref "SW3") (pin "2") (pinfunction "2_2") (pintype "passive"))
      (node (ref "U7") (pin "5") (pinfunction "GPIO0_5") (pintype "passive"))
    )
    (net (code "16") (name "/G2") (class "Default")
      (node (ref "CN1") (pin "8") (pinfunction "8_8") (pintype "passive"))
      (node (ref "U7") (pin "7") (pinfunction "GPIO2_7") (pintype "passive"))
    )
    (net (code "17") (name "/G3") (class "Default")
      (node (ref "CN1") (pin "7") (pinfunction "7_7") (pintype "passive"))
      (node (ref "U7") (pin "8") (pinfunction "GPIO3_8") (pintype "passive"))
    )
    (net (code "18") (name "/G4") (class "Default")
      (node (ref "CN1") (pin "6") (pinfunction "6_6") (pintype "passive"))
      (node (ref "U7") (pin "9") (pinfunction "GPIO4_9") (pintype "passive"))
    )
    (net (code "19") (name "/G5") (class "Default")
      (node (ref "CN1") (pin "5") (pinfunction "5_5") (pintype "passive"))
      (node (ref "U7") (pin "10") (pinfunction "GPIO5_10") (pintype "passive"))
    )
    (net (code "20") (name "/G6") (class "Default")
      (node (ref "CN1") (pin "4") (pinfunction "4_4") (pintype "passive"))
      (node (ref "U7") (pin "11") (pinfunction "GPIO6_11") (pintype "passive"))
    )
    (net (code "21") (name "/G7") (class "Default")
      (node (ref "CN1") (pin "3") (pinfunction "3_3") (pintype "passive"))
      (node (ref "U7") (pin "12") (pinfunction "GPIO7_12") (pintype "passive"))
    )
    (net (code "22") (name "/G8") (class "Default")
      (node (ref "CN1") (pin "2") (pinfunction "2_2") (pintype "passive"))
      (node (ref "U7") (pin "13") (pinfunction "GPIO8_13") (pintype "passive"))
    )
    (net (code "23") (name "/G9") (class "Default")
      (node (ref "CN1") (pin "1") (pinfunction "1_1") (pintype "passive"))
      (node (ref "U7") (pin "14") (pinfunction "GPIO9_14") (pintype "passive"))
    )
    (net (code "24") (name "/G10") (class "Default")
      (node (ref "CN1") (pin "9") (pinfunction "9_9") (pintype "passive"))
      (node (ref "U7") (pin "15") (pinfunction "GPIO10_15") (pintype "passive"))
    )
    (net (code "25") (name "/G11") (class "Default")
      (node (ref "CN1") (pin "10") (pinfunction "10_10") (pintype "passive"))
      (node (ref "U7") (pin "16") (pinfunction "GPIO11_16") (pintype "passive"))
    )
    (net (code "26") (name "/G12") (class "Default")
      (node (ref "CN1") (pin "11") (pinfunction "11_11") (pintype "passive"))
      (node (ref "U7") (pin "17") (pinfunction "GPIO12_17") (pintype "passive"))
    )
    (net (code "27") (name "/G13") (class "Default")
      (node (ref "CN1") (pin "12") (pinfunction "12_12") (pintype "passive"))
      (node (ref "U7") (pin "18") (pinfunction "GPIO13_18") (pintype "passive"))
    )
    (net (code "28") (name "/G14") (class "Default")
      (node (ref "CN1") (pin "14") (pinfunction "14_14") (pintype "passive"))
      (node (ref "U7") (pin "19") (pinfunction "GPIO14_19") (pintype "passive"))
    )
    (net (code "29") (name "/G15") (class "Default")
      (node (ref "CN1") (pin "21") (pinfunction "21_21") (pintype "passive"))
      (node (ref "U7") (pin "21") (pinfunction "XTAL_32K_P_21") (pintype "passive"))
    )
    (net (code "30") (name "/G16") (class "Default")
      (node (ref "CN1") (pin "22") (pinfunction "22_22") (pintype "passive"))
      (node (ref "R18") (pin "2") (pinfunction "2_2") (pintype "passive"))
      (node (ref "U7") (pin "22") (pinfunction "XTAL_32K_N_22") (pintype "passive"))
    )
    (net (code "31") (name "/G17") (class "Default")
      (node (ref "Q4") (pin "1") (pinfunction "G_1") (pintype "passive"))
      (node (ref "U7") (pin "23") (pinfunction "GPIO17_23") (pintype "passive"))
    )
    (net (code "32") (name "/G18") (class "Default")
      (node (ref "CN1") (pin "20") (pinfunction "20_20") (pintype "passive"))
      (node (ref "R19") (pin "2") (pinfunction "2_2") (pintype "passive"))
      (node (ref "U1") (pin "C3") (pinfunction "SDA_C3") (pintype "passive"))
      (node (ref "U2") (pin "4") (pinfunction "SDA_4") (pintype "passive"))
      (node (ref "U6") (pin "4") (pinfunction "SDA/SDI/SDO_4") (pintype "passive"))
      (node (ref "U7") (pin "24") (pinfunction "GPIO18_24") (pintype "passive"))
    )
    (net (code "33") (name "/G21") (class "Default")
      (node (ref "CN1") (pin "19") (pinfunction "19_19") (pintype "passive"))
      (node (ref "R20") (pin "2") (pinfunction "2_2") (pintype "passive"))
      (node (ref "U1") (pin "B3") (pinfunction "SCL_B3") (pintype "passive"))
      (node (ref "U2") (pin "5") (pinfunction "SCL_5") (pintype "passive"))
      (node (ref "U6") (pin "1") (pinfunction "SCL/SPC_1") (pintype "passive"))
      (node (ref "U7") (pin "27") (pinfunction "GP1O21_27") (pintype "passive"))
    )
    (net (code "34") (name "/G39") (class "Default")
      (node (ref "CARD1") (pin "9") (pinfunction "9_9") (pintype "passive"))
      (node (ref "R17") (pin "1") (pinfunction "1_1") (pintype "passive"))
      (node (ref "U7") (pin "44") (pinfunction "MTCK_44") (pintype "passive"))
    )
    (net (code "35") (name "/G40") (class "Default")
      (node (ref "CARD1") (pin "7") (pinfunction "DAT0_7") (pintype "passive"))
      (node (ref "R15") (pin "2") (pinfunction "2_2") (pintype "passive"))
      (node (ref "U7") (pin "45") (pinfunction "MTDO_45") (pintype "passive"))
    )
    (net (code "36") (name "/G41") (class "Default")
      (node (ref "CARD1") (pin "5") (pinfunction "CLK_5") (pintype "passive"))
      (node (ref "R14") (pin "2") (pinfunction "2_2") (pintype "passive"))
      (node (ref "U7") (pin "47") (pinfunction "MTDI_47") (pintype "passive"))
    )
    (net (code "37") (name "/G42") (class "Default")
      (node (ref "CARD1") (pin "3") (pinfunction "CMD_3") (pintype "passive"))
      (node (ref "R13") (pin "2") (pinfunction "2_2") (pintype "passive"))
      (node (ref "U7") (pin "48") (pinfunction "MTMS_48") (pintype "passive"))
    )
    (net (code "38") (name "/G48") (class "Default")
      (node (ref "Q2") (pin "1") (pinfunction "G_1") (pintype "passive"))
      (node (ref "R22") (pin "2") (pinfunction "2_2") (pintype "passive"))
      (node (ref "U7") (pin "36") (pinfunction "SPICLK_N_36") (pintype "passive"))
    )
    (net (code "39") (name "/LEDA") (class "Default")
      (node (ref "CN1") (pin "17") (pinfunction "17_17") (pintype "passive"))
      (node (ref "R10") (pin "1") (pinfunction "1_1") (pintype "passive"))
    )
    (net (code "40") (name "/LEDK") (class "Default")
      (node (ref "CN1") (pin "16") (pinfunction "16_16") (pintype "passive"))
      (node (ref "Q4") (pin "3") (pinfunction "D_3") (pintype "passive"))
    )
    (net (code "41") (name "/USB_N") (class "Default")
      (node (ref "U3") (pin "4") (pinfunction "HSD1-_4") (pintype "passive"))
      (node (ref "USB1") (pin "A7") (pinfunction "DN1_A7") (pintype "passive"))
      (node (ref "USB1") (pin "B7") (pinfunction "DN2_B7") (pintype "passive"))
      (node (ref "USB2") (pin "A7") (pinfunction "DN1_A7") (pintype "passive"))
      (node (ref "USB2") (pin "B7") (pinfunction "DN2_B7") (pintype "passive"))
    )
    (net (code "42") (name "/USB_P") (class "Default")
      (node (ref "U3") (pin "5") (pinfunction "HSD1+_5") (pintype "passive"))
      (node (ref "USB1") (pin "A6") (pinfunction "DP1_A6") (pintype "passive"))
      (node (ref "USB1") (pin "B6") (pinfunction "DP2_B6") (pintype "passive"))
      (node (ref "USB2") (pin "A6") (pinfunction "DP1_A6") (pintype "passive"))
      (node (ref "USB2") (pin "B6") (pinfunction "DP2_B6") (pintype "passive"))
    )
    (net (code "43") (name "GND") (class "Default")
      (node (ref "C1") (pin "1") (pinfunction "1_1") (pintype "passive"))
      (node (ref "C11") (pin "2") (pinfunction "2_2") (pintype "passive"))
      (node (ref "C12") (pin "1") (pinfunction "1_1") (pintype "passive"))
      (node (ref "C13") (pin "1") (pinfunction "1_1") (pintype "passive"))
      (node (ref "C14") (pin "2") (pinfunction "2_2") (pintype "passive"))
      (node (ref "C15") (pin "1") (pinfunction "1_1") (pintype "passive"))
      (node (ref "C16") (pin "2") (pinfunction "2_2") (pintype "passive"))
      (node (ref "C17") (pin "1") (pinfunction "1_1") (pintype "passive"))
      (node (ref "C18") (pin "1") (pinfunction "1_1") (pintype "passive"))
      (node (ref "C19") (pin "1") (pinfunction "1_1") (pintype "passive"))
      (node (ref "C2") (pin "1") (pinfunction "1_1") (pintype "passive"))
      (node (ref "C20") (pin "1") (pinfunction "1_1") (pintype "passive"))
      (node (ref "C21") (pin "2") (pinfunction "2_2") (pintype "passive"))
      (node (ref "C22") (pin "1") (pinfunction "1_1") (pintype "passive"))
      (node (ref "C23") (pin "2") (pinfunction "2_2") (pintype "passive"))
      (node (ref "C24") (pin "1") (pinfunction "1_1") (pintype "passive"))
      (node (ref "C25") (pin "1") (pinfunction "1_1") (pintype "passive"))
      (node (ref "C26") (pin "2") (pinfunction "2_2") (pintype "passive"))
      (node (ref "C27") (pin "1") (pinfunction "1_1") (pintype "passive"))
      (node (ref "C28") (pin "1") (pinfunction "1_1") (pintype "passive"))
      (node (ref "C29") (pin "1") (pinfunction "1_1") (pintype "passive"))
      (node (ref "C3") (pin "1") (pinfunction "1_1") (pintype "passive"))
      (node (ref "C30") (pin "2") (pinfunction "2_2") (pintype "passive"))
      (node (ref "C31") (pin "1") (pinfunction "1_1") (pintype "passive"))
      (node (ref "C32") (pin "1") (pinfunction "1_1") (pintype "passive"))
      (node (ref "C33") (pin "1") (pinfunction "1_1") (pintype "passive"))
      (node (ref "C34") (pin "2") (pinfunction "2_2") (pintype "passive"))
      (node (ref "C35") (pin "2") (pinfunction "2_2") (pintype "passive"))
      (node (ref "C36") (pin "2") (pinfunction "2_2") (pintype "passive"))
      (node (ref "C38") (pin "1") (pinfunction "1_1") (pintype "passive"))
      (node (ref "C39") (pin "2") (pinfunction "2_2") (pintype "passive"))
      (node (ref "C4") (pin "1") (pinfunction "1_1") (pintype "passive"))
      (node (ref "C5") (pin "2") (pinfunction "2_2") (pintype "passive"))
      (node (ref "C6") (pin "1") (pinfunction "1_1") (pintype "passive"))
      (node (ref "C7") (pin "2") (pinfunction "2_2") (pintype "passive"))
      (node (ref "C9") (pin "2") (pinfunction "2_2") (pintype "passive"))
      (node (ref "CARD1") (pin "10") (pinfunction "10_10") (pintype "passive"))
      (node (ref "CARD1") (pin "11") (pinfunction "EH_11") (pintype "passive"))
      (node (ref "CARD1") (pin "6") (pinfunction "VSS_6") (pintype "passive"))
      (node (ref "CN1") (pin "13") (pinfunction "13_13") (pintype "passive"))
      (node (ref "CN1") (pin "18") (pinfunction "18_18") (pintype "passive"))
      (node (ref "CN1") (pin "24") (pinfunction "24_24") (pintype "passive"))
      (node (ref "CN1") (pin "25") (pinfunction "25_25") (pintype "passive"))
      (node (ref "CN1") (pin "26") (pinfunction "26_26") (pintype "passive"))
      (node (ref "CN1") (pin "27") (pinfunction "27_27") (pintype "passive"))
      (node (ref "CN1") (pin "28") (pinfunction "28_28") (pintype "passive"))
      (node (ref "D4") (pin "1") (pinfunction "1_1") (pintype "passive"))
      (node (ref "J2") (pin "1") (pinfunction "1_1") (pintype "passive"))
      (node (ref "Q2") (pin "2") (pinfunction "S_2") (pintype "passive"))
      (node (ref "Q3") (pin "2") (pinfunction "S_2") (pintype "passive"))
      (node (ref "Q4") (pin "2") (pinfunction "S_2") (pintype "passive"))
      (node (ref "R22") (pin "1") (pinfunction "1_1") (pintype "passive"))
      (node (ref "R8") (pin "1") (pinfunction "1_1") (pintype "passive"))
      (node (ref "R9") (pin "1") (pinfunction "1_1") (pintype "passive"))
      (node (ref "SW1") (pin "1") (pinfunction "1_1") (pintype "passive"))
      (node (ref "SW1") (pin "2") (pinfunction "2_2") (pintype "passive"))
      (node (ref "SW1") (pin "4") (pinfunction "4_4") (pintype "passive"))
      (node (ref "SW1") (pin "5") (pinfunction "5_5") (pintype "passive"))
      (node (ref "SW2") (pin "1") (pinfunction "1_1") (pintype "passive"))
      (node (ref "SW3") (pin "1") (pinfunction "1_1") (pintype "passive"))
      (node (ref "U1") (pin "C2") (pinfunction "GND_C2") (pintype "passive"))
      (node (ref "U2") (pin "1") (pinfunction "A1_1") (pintype "passive"))
      (node (ref "U2") (pin "2") (pinfunction "A0_2") (pintype "passive"))
      (node (ref "U2") (pin "7") (pinfunction "GND_7") (pintype "passive"))
      (node (ref "U3") (pin "3") (pinfunction "GND_3") (pintype "passive"))
      (node (ref "U3") (pin "8") (pinfunction "OE#_8") (pintype "passive"))
      (node (ref "U4") (pin "4") (pinfunction "GND_4") (pintype "passive"))
      (node (ref "U5") (pin "4") (pinfunction "Feedpoint_4") (pintype "passive"))
      (node (ref "U6") (pin "6") (pinfunction "GND_6") (pintype "passive"))
      (node (ref "U6") (pin "7") (pinfunction "RES_7") (pintype "passive"))
      (node (ref "U6") (pin "8") (pinfunction "GND_8") (pintype "passive"))
      (node (ref "U7") (pin "57") (pinfunction "GND_57") (pintype "passive"))
      (node (ref "U8") (pin "1") (pinfunction "K_1") (pintype "passive"))
      (node (ref "USB1") (pin "0") (pinfunction "15_0") (pintype "passive"))
      (node (ref "USB1") (pin "A1") (pinfunction "GND_A1") (pintype "passive"))
      (node (ref "USB1") (pin "A12") (pinfunction "GND_A12") (pintype "passive"))
      (node (ref "USB2") (pin "12") (pinfunction "12_12") (pintype "passive"))
      (node (ref "USB2") (pin "13") (pinfunction "13_13") (pintype "passive"))
      (node (ref "USB2") (pin "14") (pinfunction "14_14") (pintype "passive"))
      (node (ref "USB2") (pin "15") (pinfunction "15_15") (pintype "passive"))
      (node (ref "USB2") (pin "A1B12") (pinfunction "GND_A1B12") (pintype "passive"))
      (node (ref "USB2") (pin "B1A12") (pinfunction "GND_B1A12") (pintype "passive"))
      (node (ref "X1") (pin "2") (pinfunction "2_2") (pintype "passive"))
      (node (ref "X1") (pin "4") (pinfunction "4_4") (pintype "passive"))
    )
    (net (code "44") (name "Net-(C30-Pad1)") (class "Default")
      (node (ref "C30") (pin "1") (pinfunction "1_1") (pintype "passive"))
      (node (ref "L2") (pin "2") (pinfunction "2_2") (pintype "passive"))
      (node (ref "U7") (pin "2") (pinfunction "VDD3P3_2") (pintype "passive"))
      (node (ref "U7") (pin "3") (pinfunction "VDD3P3_3") (pintype "passive"))
    )
    (net (code "45") (name "Net-(D1-A)") (class "Default")
      (node (ref "BUZZER1") (pin "2") (pinfunction "2_2") (pintype "passive"))
      (node (ref "D1") (pin "2") (pinfunction "A_2") (pintype "passive"))
      (node (ref "Q3") (pin "3") (pinfunction "D_3") (pintype "passive"))
    )
    (net (code "46") (name "Net-(Q1-G)") (class "Default")
      (node (ref "Q1") (pin "4") (pinfunction "G_4") (pintype "passive"))
      (node (ref "R5") (pin "1") (pinfunction "1_1") (pintype "passive"))
      (node (ref "R6") (pin "2") (pinfunction "2_2") (pintype "passive"))
    )
    (net (code "47") (name "Net-(Q2-D)") (class "Default")
      (node (ref "Q2") (pin "3") (pinfunction "D_3") (pintype "passive"))
      (node (ref "R6") (pin "1") (pinfunction "1_1") (pintype "passive"))
    )
    (net (code "48") (name "Net-(U2-IN+)") (class "Default")
      (node (ref "C8") (pin "2") (pinfunction "2_2") (pintype "passive"))
      (node (ref "R2") (pin "1") (pinfunction "1_1") (pintype "passive"))
      (node (ref "U2") (pin "10") (pinfunction "IN+_10") (pintype "passive"))
    )
    (net (code "49") (name "Net-(U2-IN–)") (class "Default")
      (node (ref "C8") (pin "1") (pinfunction "1_1") (pintype "passive"))
      (node (ref "R3") (pin "1") (pinfunction "1_1") (pintype "passive"))
      (node (ref "U2") (pin "9") (pinfunction "IN–_9") (pintype "passive"))
    )
    (net (code "50") (name "Net-(U3-S)") (class "Default")
      (node (ref "R4") (pin "1") (pinfunction "1_1") (pintype "passive"))
      (node (ref "SW1") (pin "3") (pinfunction "3_3") (pintype "passive"))
      (node (ref "U3") (pin "10") (pinfunction "S_10") (pintype "passive"))
    )
    (net (code "51") (name "Net-(U4-BST)") (class "Default")
      (node (ref "C10") (pin "2") (pinfunction "2_2") (pintype "passive"))
      (node (ref "U4") (pin "6") (pinfunction "BST_6") (pintype "passive"))
    )
    (net (code "52") (name "Net-(U4-FB)") (class "Default")
      (node (ref "R7") (pin "1") (pinfunction "1_1") (pintype "passive"))
      (node (ref "R9") (pin "2") (pinfunction "2_2") (pintype "passive"))
      (node (ref "U4") (pin "8") (pinfunction "FB_8") (pintype "passive"))
    )
    (net (code "53") (name "Net-(U4-RT)") (class "Default")
      (node (ref "R8") (pin "2") (pinfunction "2_2") (pintype "passive"))
      (node (ref "U4") (pin "1") (pinfunction "RT_1") (pintype "passive"))
    )
    (net (code "54") (name "Net-(U4-SS)") (class "Default")
      (node (ref "C19") (pin "2") (pinfunction "2_2") (pintype "passive"))
      (node (ref "U4") (pin "7") (pinfunction "SS_7") (pintype "passive"))
    )
    (net (code "55") (name "Net-(U4-SW)") (class "Default")
      (node (ref "C10") (pin "1") (pinfunction "1_1") (pintype "passive"))
      (node (ref "L1") (pin "1") (pinfunction "1_1") (pintype "passive"))
      (node (ref "U4") (pin "5") (pinfunction "SW_5") (pintype "passive"))
    )
    (net (code "56") (name "Net-(U5-Radiatorelectrode)") (class "Default")
      (node (ref "C20") (pin "2") (pinfunction "2_2") (pintype "passive"))
      (node (ref "U5") (pin "1") (pinfunction "Radiatorelectrode_1") (pintype "passive"))
    )
    (net (code "57") (name "Net-(U6-CS)") (class "Default")
      (node (ref "R16") (pin "1") (pinfunction "1_1") (pintype "passive"))
      (node (ref "U6") (pin "2") (pinfunction "CS_2") (pintype "passive"))
    )
    (net (code "58") (name "Net-(U7-LNA_IN)") (class "Default")
      (node (ref "C21") (pin "1") (pinfunction "1_1") (pintype "passive"))
      (node (ref "U5") (pin "2") (pinfunction "Dummypad_2") (pintype "passive"))
      (node (ref "U5") (pin "5") (pinfunction "Dummypad_5") (pintype "passive"))
      (node (ref "U7") (pin "1") (pinfunction "LNA_IN_1") (pintype "passive"))
    )
    (net (code "59") (name "Net-(U7-VDD_SPI)") (class "Default")
      (node (ref "C38") (pin "2") (pinfunction "2_2") (pintype "passive"))
      (node (ref "U7") (pin "29") (pinfunction "VDD_SPI_29") (pintype "passive"))
    )
    (net (code "60") (name "Net-(U7-XTAL_N)") (class "Default")
      (node (ref "C32") (pin "2") (pinfunction "2_2") (pintype "passive"))
      (node (ref "U7") (pin "53") (pinfunction "XTAL_N_53") (pintype "passive"))
      (node (ref "X1") (pin "1") (pinfunction "OSC1_1") (pintype "passive"))
    )
    (net (code "61") (name "Net-(U7-XTAL_P)") (class "Default")
      (node (ref "L3") (pin "1") (pinfunction "1_1") (pintype "passive"))
      (node (ref "U7") (pin "54") (pinfunction "XTAL_P_54") (pintype "passive"))
    )
    (net (code "62") (name "Net-(U8-A)") (class "Default")
      (node (ref "J1") (pin "1") (pinfunction "1_1") (pintype "passive"))
      (node (ref "Q1") (pin "5") (pinfunction "D_5") (pintype "passive"))
      (node (ref "Q1") (pin "6") (pinfunction "D_6") (pintype "passive"))
      (node (ref "Q1") (pin "7") (pinfunction "D_7") (pintype "passive"))
      (node (ref "Q1") (pin "8") (pinfunction "D_8") (pintype "passive"))
      (node (ref "Q1") (pin "9") (pinfunction "D_9") (pintype "passive"))
      (node (ref "U8") (pin "2") (pinfunction "A_2") (pintype "passive"))
    )
    (net (code "63") (name "Net-(X1-OSC2)") (class "Default")
      (node (ref "C31") (pin "2") (pinfunction "2_2") (pintype "passive"))
      (node (ref "L3") (pin "2") (pinfunction "2_2") (pintype "passive"))
      (node (ref "X1") (pin "3") (pinfunction "OSC2_3") (pintype "passive"))
    )
    (net (code "64") (name "VBUS") (class "Default")
      (node (ref "C12") (pin "2") (pinfunction "2_2") (pintype "passive"))
      (node (ref "C13") (pin "2") (pinfunction "2_2") (pintype "passive"))
      (node (ref "C14") (pin "1") (pinfunction "1_1") (pintype "passive"))
      (node (ref "R1") (pin "1") (pinfunction "1_1") (pintype "passive"))
      (node (ref "R2") (pin "2") (pinfunction "2_2") (pintype "passive"))
      (node (ref "U1") (pin "A2") (pinfunction "VBUS_A2") (pintype "passive"))
      (node (ref "U2") (pin "8") (pinfunction "VBUS_8") (pintype "passive"))
      (node (ref "U4") (pin "3") (pinfunction "VIN_3") (pintype "passive"))
      (node (ref "USB1") (pin "A4") (pinfunction "VBUS_A4") (pintype "passive"))
      (node (ref "USB1") (pin "A9") (pinfunction "VBUS_A9") (pintype "passive"))
    )
    (net (code "65") (name "VBUS_OUT") (class "Default")
      (node (ref "C1") (pin "2") (pinfunction "2_2") (pintype "passive"))
      (node (ref "C2") (pin "2") (pinfunction "2_2") (pintype "passive"))
      (node (ref "C3") (pin "2") (pinfunction "2_2") (pintype "passive"))
      (node (ref "C4") (pin "2") (pinfunction "2_2") (pintype "passive"))
      (node (ref "Q1") (pin "1") (pinfunction "S_1") (pintype "passive"))
      (node (ref "Q1") (pin "2") (pinfunction "S_2") (pintype "passive"))
      (node (ref "Q1") (pin "3") (pinfunction "S_3") (pintype "passive"))
      (node (ref "R1") (pin "2") (pinfunction "2_2") (pintype "passive"))
      (node (ref "R3") (pin "2") (pinfunction "2_2") (pintype "passive"))
      (node (ref "R5") (pin "2") (pinfunction "2_2") (pintype "passive"))
      (node (ref "USB2") (pin "A4B9") (pinfunction "VBUS_A4B9") (pintype "passive"))
      (node (ref "USB2") (pin "B4A9") (pinfunction "VBUS_B4A9") (pintype "passive"))
    )
    (net (code "66") (name "unconnected-(CARD1-CD{slash}DAT3-Pad2)") (class "Default")
      (node (ref "CARD1") (pin "2") (pinfunction "CD/DAT3_2") (pintype "passive+no_connect"))
    )
    (net (code "67") (name "unconnected-(CARD1-DAT1-Pad8)") (class "Default")
      (node (ref "CARD1") (pin "8") (pinfunction "DAT1_8") (pintype "passive+no_connect"))
    )
    (net (code "68") (name "unconnected-(CARD1-DAT2-Pad1)") (class "Default")
      (node (ref "CARD1") (pin "1") (pinfunction "DAT2_1") (pintype "passive+no_connect"))
    )
    (net (code "69") (name "unconnected-(SW2-Pad3)") (class "Default")
      (node (ref "SW2") (pin "3") (pinfunction "3_3") (pintype "passive"))
    )
    (net (code "70") (name "unconnected-(SW2-Pad4)") (class "Default")
      (node (ref "SW2") (pin "4") (pinfunction "4_4") (pintype "passive"))
    )
    (net (code "71") (name "unconnected-(SW3-Pad3)") (class "Default")
      (node (ref "SW3") (pin "3") (pinfunction "3_3") (pintype "passive"))
    )
    (net (code "72") (name "unconnected-(SW3-Pad4)") (class "Default")
      (node (ref "SW3") (pin "4") (pinfunction "4_4") (pintype "passive"))
    )
    (net (code "73") (name "unconnected-(U1-VCONN-PadB1)") (class "Default")
      (node (ref "U1") (pin "B1") (pinfunction "VCONN_B1") (pintype "passive+no_connect"))
    )
    (net (code "74") (name "unconnected-(U2-ALERT-Pad3)") (class "Default")
      (node (ref "U2") (pin "3") (pinfunction "ALERT_3") (pintype "passive+no_connect"))
    )
    (net (code "75") (name "unconnected-(U3-HSD2+-Pad7)") (class "Default")
      (node (ref "U3") (pin "7") (pinfunction "HSD2+_7") (pintype "passive+no_connect"))
    )
    (net (code "76") (name "unconnected-(U3-HSD2--Pad6)") (class "Default")
      (node (ref "U3") (pin "6") (pinfunction "HSD2-_6") (pintype "passive+no_connect"))
    )
    (net (code "77") (name "unconnected-(U4-EN-Pad2)") (class "Default")
      (node (ref "U4") (pin "2") (pinfunction "EN_2") (pintype "passive+no_connect"))
    )
    (net (code "78") (name "unconnected-(U6-INT1-Pad12)") (class "Default")
      (node (ref "U6") (pin "12") (pinfunction "INT1_12") (pintype "passive"))
    )
    (net (code "79") (name "unconnected-(U6-INT2-Pad11)") (class "Default")
      (node (ref "U6") (pin "11") (pinfunction "INT2_11") (pintype "passive"))
    )
    (net (code "80") (name "unconnected-(U6-NC-Pad5)") (class "Default")
      (node (ref "U6") (pin "5") (pinfunction "NC_5") (pintype "passive"))
    )
    (net (code "81") (name "unconnected-(U6-SDO{slash}SA0-Pad3)") (class "Default")
      (node (ref "U6") (pin "3") (pinfunction "SDO/SA0_3") (pintype "passive"))
    )
    (net (code "82") (name "unconnected-(U7-GPIO45-Pad51)") (class "Default")
      (node (ref "U7") (pin "51") (pinfunction "GPIO45_51") (pintype "passive+no_connect"))
    )
    (net (code "83") (name "unconnected-(U7-GPIO46-Pad52)") (class "Default")
      (node (ref "U7") (pin "52") (pinfunction "GPIO46_52") (pintype "passive+no_connect"))
    )
    (net (code "84") (name "unconnected-(U7-SPICLK-Pad33)") (class "Default")
      (node (ref "U7") (pin "33") (pinfunction "SPICLK_33") (pintype "passive+no_connect"))
    )
    (net (code "85") (name "unconnected-(U7-SPICS0-Pad32)") (class "Default")
      (node (ref "U7") (pin "32") (pinfunction "SPICS0_32") (pintype "passive+no_connect"))
    )
    (net (code "86") (name "unconnected-(U7-SPICS1-Pad28)") (class "Default")
      (node (ref "U7") (pin "28") (pinfunction "SPICS1_28") (pintype "passive+no_connect"))
    )
    (net (code "87") (name "unconnected-(U7-SPID-Pad35)") (class "Default")
      (node (ref "U7") (pin "35") (pinfunction "SPID_35") (pintype "passive+no_connect"))
    )
    (net (code "88") (name "unconnected-(U7-SPIHD-Pad30)") (class "Default")
      (node (ref "U7") (pin "30") (pinfunction "SPIHD_30") (pintype "passive+no_connect"))
    )
    (net (code "89") (name "unconnected-(U7-SPIQ-Pad34)") (class "Default")
      (node (ref "U7") (pin "34") (pinfunction "SPIQ_34") (pintype "passive+no_connect"))
    )
    (net (code "90") (name "unconnected-(U7-SPIWP-Pad31)") (class "Default")
      (node (ref "U7") (pin "31") (pinfunction "SPIWP_31") (pintype "passive+no_connect"))
    )
    (net (code "91") (name "unconnected-(U7-U0RXD-Pad50)") (class "Default")
      (node (ref "U7") (pin "50") (pinfunction "U0RXD_50") (pintype "passive+no_connect"))
    )
    (net (code "92") (name "unconnected-(U7-U0TXD-Pad49)") (class "Default")
      (node (ref "U7") (pin "49") (pinfunction "U0TXD_49") (pintype "passive+no_connect"))
    )
    (net (code "93") (name "unconnected-(USB1-SBU1-PadA8)") (class "Default")
      (node (ref "USB1") (pin "A8") (pinfunction "SBU1_A8") (pintype "passive"))
    )
    (net (code "94") (name "unconnected-(USB1-SBU2-PadB8)") (class "Default")
      (node (ref "USB1") (pin "B8") (pinfunction "SBU2_B8") (pintype "passive"))
    )
    (net (code "95") (name "unconnected-(USB2-SBU1-PadA8)") (class "Default")
      (node (ref "USB2") (pin "A8") (pinfunction "SBU1_A8") (pintype "passive"))
    )
    (net (code "96") (name "unconnected-(USB2-SBU2-PadB8)") (class "Default")
      (node (ref "USB2") (pin "B8") (pinfunction "SBU2_B8") (pintype "passive"))
    )
  )
)
